# lo.net
KiCad netlist of a schematic drawn in EAGLE
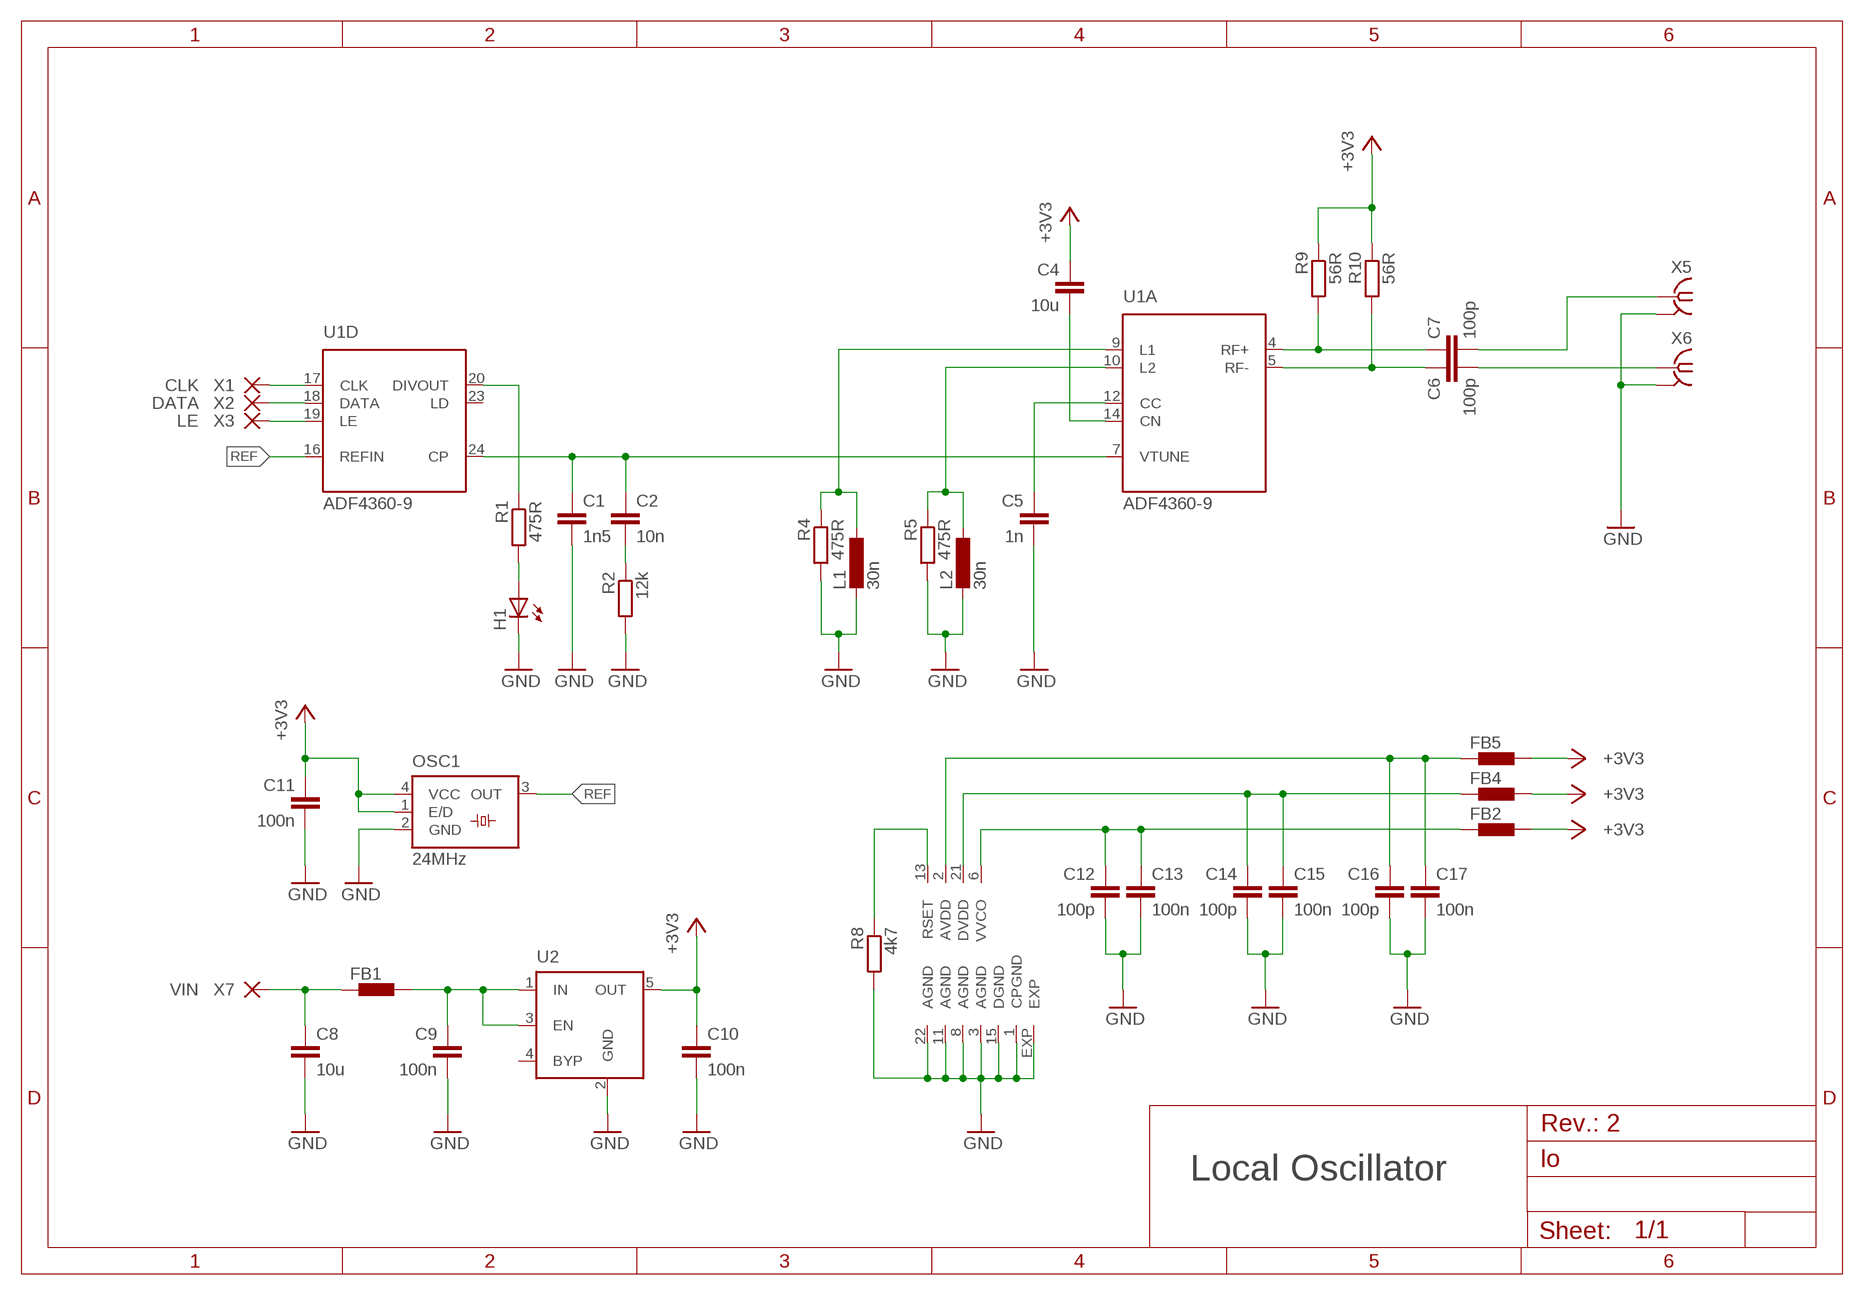
[diagram p0: schematic, sheet 1]

(export (version "E")
  (design (tool "Eeschema 10.0.6"))
  (components
    (comp (ref "C1")
      (value "1n5")
      (footprint "eagle-import:C0402")
      (libsource (lib "eagle-import") (part "C-EUC0402"))
    )
    (comp (ref "C2")
      (value "10n")
      (footprint "eagle-import:C0603")
      (libsource (lib "eagle-import") (part "C-EUC0603"))
    )
    (comp (ref "C4")
      (value "10u")
      (footprint "eagle-import:C0805")
      (libsource (lib "eagle-import") (part "C-EUC0805"))
    )
    (comp (ref "C5")
      (value "1n")
      (footprint "eagle-import:C0603")
      (libsource (lib "eagle-import") (part "C-EUC0603"))
    )
    (comp (ref "C6")
      (value "100p")
      (footprint "eagle-import:C0402")
      (libsource (lib "eagle-import") (part "C-EUC0402"))
    )
    (comp (ref "C7")
      (value "100p")
      (footprint "eagle-import:C0402")
      (libsource (lib "eagle-import") (part "C-EUC0402"))
    )
    (comp (ref "C8")
      (value "10u")
      (footprint "eagle-import:C0805")
      (libsource (lib "eagle-import") (part "C-EUC0805"))
    )
    (comp (ref "C9")
      (value "100n")
      (footprint "eagle-import:C0603")
      (libsource (lib "eagle-import") (part "C-EUC0603"))
    )
    (comp (ref "C10")
      (value "100n")
      (footprint "eagle-import:C0603")
      (libsource (lib "eagle-import") (part "C-EUC0603"))
    )
    (comp (ref "C11")
      (value "100n")
      (footprint "eagle-import:C0603")
      (libsource (lib "eagle-import") (part "C-EUC0603"))
    )
    (comp (ref "C12")
      (value "100p")
      (footprint "eagle-import:C0603")
      (libsource (lib "eagle-import") (part "C-EUC0603"))
    )
    (comp (ref "C13")
      (value "100n")
      (footprint "eagle-import:C0603")
      (libsource (lib "eagle-import") (part "C-EUC0603"))
    )
    (comp (ref "C14")
      (value "100p")
      (footprint "eagle-import:C0603")
      (libsource (lib "eagle-import") (part "C-EUC0603"))
    )
    (comp (ref "C15")
      (value "100n")
      (footprint "eagle-import:C0603")
      (libsource (lib "eagle-import") (part "C-EUC0603"))
    )
    (comp (ref "C16")
      (value "100p")
      (footprint "eagle-import:C0603")
      (libsource (lib "eagle-import") (part "C-EUC0603"))
    )
    (comp (ref "C17")
      (value "100n")
      (footprint "eagle-import:C0603")
      (libsource (lib "eagle-import") (part "C-EUC0603"))
    )
    (comp (ref "FB1")
      (value "BML15H")
      (footprint "eagle-import:R0603")
      (libsource (lib "eagle-import") (part "BML15H"))
    )
    (comp (ref "FB2")
      (value "BML15H")
      (footprint "eagle-import:R0603")
      (libsource (lib "eagle-import") (part "BML15H"))
    )
    (comp (ref "FB4")
      (value "BML15H")
      (footprint "eagle-import:R0603")
      (libsource (lib "eagle-import") (part "BML15H"))
    )
    (comp (ref "FB5")
      (value "BML15H")
      (footprint "eagle-import:R0603")
      (libsource (lib "eagle-import") (part "BML15H"))
    )
    (comp (ref "H1")
      (value "PL006-WCR13")
      (footprint "eagle-import:SOT23")
      (libsource (lib "eagle-import") (part "PL006-WCR13"))
    )
    (comp (ref "L1")
      (value "30n")
      (footprint "eagle-import:L2012C")
      (libsource (lib "eagle-import") (part "L-EUL2012C"))
    )
    (comp (ref "L2")
      (value "30n")
      (footprint "eagle-import:L2012C")
      (libsource (lib "eagle-import") (part "L-EUL2012C"))
    )
    (comp (ref "OSC1")
      (value "24MHz")
      (footprint "eagle-import:SM77H")
      (libsource (lib "eagle-import") (part "SM77H"))
    )
    (comp (ref "R1")
      (value "475R")
      (footprint "eagle-import:R1206")
      (libsource (lib "eagle-import") (part "R-EU_R1206"))
    )
    (comp (ref "R2")
      (value "12k")
      (footprint "eagle-import:R0603")
      (libsource (lib "eagle-import") (part "R-EU_R0603"))
    )
    (comp (ref "R4")
      (value "475R")
      (footprint "eagle-import:R0603")
      (libsource (lib "eagle-import") (part "R-EU_R0603"))
    )
    (comp (ref "R5")
      (value "475R")
      (footprint "eagle-import:R0603")
      (libsource (lib "eagle-import") (part "R-EU_R0603"))
    )
    (comp (ref "R8")
      (value "4k7")
      (footprint "eagle-import:R0603")
      (libsource (lib "eagle-import") (part "R-EU_R0603"))
    )
    (comp (ref "R9")
      (value "56R")
      (footprint "eagle-import:R0603")
      (libsource (lib "eagle-import") (part "R-EU_R0603"))
    )
    (comp (ref "R10")
      (value "56R")
      (footprint "eagle-import:R0603")
      (libsource (lib "eagle-import") (part "R-EU_R0603"))
    )
    (comp (ref "U1")
      (value "ADF4360-9")
      (footprint "eagle-import:LFCSP24")
      (libsource (lib "eagle-import") (part "ADF4360"))
    )
    (comp (ref "U2")
      (value "MIC5219XX")
      (footprint "eagle-import:SOT23-5")
      (libsource (lib "eagle-import") (part "MIC5219XX"))
    )
    (comp (ref "X1")
      (value "CLK")
      (footprint "eagle-import:SMD1,27-2,54")
      (libsource (lib "eagle-import") (part "SMD2"))
    )
    (comp (ref "X2")
      (value "DATA")
      (footprint "eagle-import:SMD1,27-2,54")
      (libsource (lib "eagle-import") (part "SMD2"))
    )
    (comp (ref "X3")
      (value "LE")
      (footprint "eagle-import:SMD1,27-2,54")
      (libsource (lib "eagle-import") (part "SMD2"))
    )
    (comp (ref "X5")
      (value "SMA-142-0701-881/886")
      (footprint "eagle-import:J502-ND-142-0701-881_886")
      (fields (field (name "MF") "JOHNSON COMPONENTS") (field (name "MPN") "142-0701-881"))
      (libsource (lib "eagle-import") (part "SMA-142-0701-881/886"))
    )
    (comp (ref "X6")
      (value "SMA-142-0701-881/886")
      (footprint "eagle-import:J502-ND-142-0701-881_886")
      (fields (field (name "MF") "JOHNSON COMPONENTS") (field (name "MPN") "142-0701-881"))
      (libsource (lib "eagle-import") (part "SMA-142-0701-881/886"))
    )
    (comp (ref "X7")
      (value "VIN")
      (footprint "eagle-import:SMD1,27-2,54")
      (libsource (lib "eagle-import") (part "SMD2"))
    )
  )
  (nets
    (net (code "1") (name "+3V3") (class "Default")
      (node (ref "C10") (pin "1") (pinfunction "1_1") (pintype "passive"))
      (node (ref "C11") (pin "1") (pinfunction "1_1") (pintype "passive"))
      (node (ref "C4") (pin "1") (pinfunction "1_1") (pintype "passive"))
      (node (ref "FB2") (pin "2") (pinfunction "2_2") (pintype "passive"))
      (node (ref "FB4") (pin "2") (pinfunction "2_2") (pintype "passive"))
      (node (ref "FB5") (pin "2") (pinfunction "2_2") (pintype "passive"))
      (node (ref "OSC1") (pin "1") (pinfunction "E/D_1") (pintype "input"))
      (node (ref "OSC1") (pin "4") (pinfunction "VCC_4") (pintype "power_in"))
      (node (ref "R10") (pin "1") (pinfunction "1_1") (pintype "passive"))
      (node (ref "R9") (pin "1") (pinfunction "1_1") (pintype "passive"))
      (node (ref "U2") (pin "5") (pinfunction "OUT_5") (pintype "output"))
    )
    (net (code "2") (name "GND") (class "Default")
      (node (ref "C1") (pin "2") (pinfunction "2_2") (pintype "passive"))
      (node (ref "C10") (pin "2") (pinfunction "2_2") (pintype "passive"))
      (node (ref "C11") (pin "2") (pinfunction "2_2") (pintype "passive"))
      (node (ref "C12") (pin "2") (pinfunction "2_2") (pintype "passive"))
      (node (ref "C13") (pin "2") (pinfunction "2_2") (pintype "passive"))
      (node (ref "C14") (pin "2") (pinfunction "2_2") (pintype "passive"))
      (node (ref "C15") (pin "2") (pinfunction "2_2") (pintype "passive"))
      (node (ref "C16") (pin "2") (pinfunction "2_2") (pintype "passive"))
      (node (ref "C17") (pin "2") (pinfunction "2_2") (pintype "passive"))
      (node (ref "C5") (pin "2") (pinfunction "2_2") (pintype "passive"))
      (node (ref "C8") (pin "2") (pinfunction "2_2") (pintype "passive"))
      (node (ref "C9") (pin "2") (pinfunction "2_2") (pintype "passive"))
      (node (ref "H1") (pin "3") (pinfunction "C_3") (pintype "passive"))
      (node (ref "L1") (pin "2") (pinfunction "2_2") (pintype "passive"))
      (node (ref "L2") (pin "2") (pinfunction "2_2") (pintype "passive"))
      (node (ref "OSC1") (pin "2") (pinfunction "GND_2") (pintype "power_in"))
      (node (ref "R2") (pin "2") (pinfunction "2_2") (pintype "passive"))
      (node (ref "R4") (pin "2") (pinfunction "2_2") (pintype "passive"))
      (node (ref "R5") (pin "2") (pinfunction "2_2") (pintype "passive"))
      (node (ref "R8") (pin "2") (pinfunction "2_2") (pintype "passive"))
      (node (ref "U1") (pin "1") (pinfunction "CPGND_1") (pintype "power_in"))
      (node (ref "U1") (pin "11") (pinfunction "AGND_11") (pintype "power_in"))
      (node (ref "U1") (pin "15") (pinfunction "DGND_15") (pintype "power_in"))
      (node (ref "U1") (pin "22") (pinfunction "AGND_22") (pintype "power_in"))
      (node (ref "U1") (pin "3") (pinfunction "AGND_3") (pintype "power_in"))
      (node (ref "U1") (pin "8") (pinfunction "AGND_8") (pintype "power_in"))
      (node (ref "U1") (pin "EXP") (pinfunction "EXP_EXP") (pintype "power_in"))
      (node (ref "U2") (pin "2") (pinfunction "GND_2") (pintype "power_in"))
      (node (ref "X5") (pin "G@1") (pinfunction "GND_G@1") (pintype "power_in"))
      (node (ref "X6") (pin "G@1") (pinfunction "GND_G@1") (pintype "power_in"))
    )
    (net (code "3") (name "Net-(C2-Pad2)") (class "Default")
      (node (ref "C2") (pin "2") (pinfunction "2_2") (pintype "passive"))
      (node (ref "R2") (pin "1") (pinfunction "1_1") (pintype "passive"))
    )
    (net (code "4") (name "Net-(C6-Pad2)") (class "Default")
      (node (ref "C6") (pin "2") (pinfunction "2_2") (pintype "passive"))
      (node (ref "X6") (pin "1") (pinfunction "1_1") (pintype "passive"))
    )
    (net (code "5") (name "Net-(C7-Pad2)") (class "Default")
      (node (ref "C7") (pin "2") (pinfunction "2_2") (pintype "passive"))
      (node (ref "X5") (pin "1") (pinfunction "1_1") (pintype "passive"))
    )
    (net (code "6") (name "Net-(H1-A)") (class "Default")
      (node (ref "H1") (pin "1") (pinfunction "A_1") (pintype "passive"))
      (node (ref "R1") (pin "2") (pinfunction "2_2") (pintype "passive"))
    )
    (net (code "7") (name "Net-(U1A-CC)") (class "Default")
      (node (ref "C5") (pin "1") (pinfunction "1_1") (pintype "passive"))
      (node (ref "U1") (pin "12") (pinfunction "CC_12") (pintype "passive"))
    )
    (net (code "8") (name "Net-(U1A-CN)") (class "Default")
      (node (ref "C4") (pin "2") (pinfunction "2_2") (pintype "passive"))
      (node (ref "U1") (pin "14") (pinfunction "CN_14") (pintype "passive"))
    )
    (net (code "9") (name "Net-(U1A-L1)") (class "Default")
      (node (ref "L1") (pin "1") (pinfunction "1_1") (pintype "passive"))
      (node (ref "R4") (pin "1") (pinfunction "1_1") (pintype "passive"))
      (node (ref "U1") (pin "9") (pinfunction "L1_9") (pintype "passive"))
    )
    (net (code "10") (name "Net-(U1A-L2)") (class "Default")
      (node (ref "L2") (pin "1") (pinfunction "1_1") (pintype "passive"))
      (node (ref "R5") (pin "1") (pinfunction "1_1") (pintype "passive"))
      (node (ref "U1") (pin "10") (pinfunction "L2_10") (pintype "passive"))
    )
    (net (code "11") (name "Net-(U1A-RF+)") (class "Default")
      (node (ref "C7") (pin "1") (pinfunction "1_1") (pintype "passive"))
      (node (ref "R9") (pin "2") (pinfunction "2_2") (pintype "passive"))
      (node (ref "U1") (pin "4") (pinfunction "RF+_4") (pintype "output"))
    )
    (net (code "12") (name "Net-(U1A-RF-)") (class "Default")
      (node (ref "C6") (pin "1") (pinfunction "1_1") (pintype "passive"))
      (node (ref "R10") (pin "2") (pinfunction "2_2") (pintype "passive"))
      (node (ref "U1") (pin "5") (pinfunction "RF-_5") (pintype "output"))
    )
    (net (code "13") (name "Net-(U1A-VTUNE)") (class "Default")
      (node (ref "C1") (pin "1") (pinfunction "1_1") (pintype "passive"))
      (node (ref "C2") (pin "1") (pinfunction "1_1") (pintype "passive"))
      (node (ref "U1") (pin "24") (pinfunction "CP_24") (pintype "output"))
      (node (ref "U1") (pin "7") (pinfunction "VTUNE_7") (pintype "input"))
    )
    (net (code "14") (name "Net-(U1B-CLK)") (class "Default")
      (node (ref "U1") (pin "17") (pinfunction "CLK_17") (pintype "input"))
      (node (ref "X1") (pin "1") (pinfunction "P_1") (pintype "passive"))
    )
    (net (code "15") (name "Net-(U1B-DATA)") (class "Default")
      (node (ref "U1") (pin "18") (pinfunction "DATA_18") (pintype "input"))
      (node (ref "X2") (pin "1") (pinfunction "P_1") (pintype "passive"))
    )
    (net (code "16") (name "Net-(U1B-DIVOUT)") (class "Default")
      (node (ref "R1") (pin "1") (pinfunction "1_1") (pintype "passive"))
      (node (ref "U1") (pin "20") (pinfunction "DIVOUT_20") (pintype "output"))
    )
    (net (code "17") (name "Net-(U1B-LE)") (class "Default")
      (node (ref "U1") (pin "19") (pinfunction "LE_19") (pintype "input"))
      (node (ref "X3") (pin "1") (pinfunction "P_1") (pintype "passive"))
    )
    (net (code "18") (name "Net-(U1C-AVDD)") (class "Default")
      (node (ref "C16") (pin "1") (pinfunction "1_1") (pintype "passive"))
      (node (ref "C17") (pin "1") (pinfunction "1_1") (pintype "passive"))
      (node (ref "FB5") (pin "1") (pinfunction "1_1") (pintype "passive"))
      (node (ref "U1") (pin "2") (pinfunction "AVDD_2") (pintype "power_in"))
    )
    (net (code "19") (name "Net-(U1C-DVDD)") (class "Default")
      (node (ref "C14") (pin "1") (pinfunction "1_1") (pintype "passive"))
      (node (ref "C15") (pin "1") (pinfunction "1_1") (pintype "passive"))
      (node (ref "FB4") (pin "1") (pinfunction "1_1") (pintype "passive"))
      (node (ref "U1") (pin "21") (pinfunction "DVDD_21") (pintype "power_in"))
    )
    (net (code "20") (name "Net-(U1C-RSET)") (class "Default")
      (node (ref "R8") (pin "1") (pinfunction "1_1") (pintype "passive"))
      (node (ref "U1") (pin "13") (pinfunction "RSET_13") (pintype "power_in"))
    )
    (net (code "21") (name "Net-(U1C-VVCO)") (class "Default")
      (node (ref "C12") (pin "1") (pinfunction "1_1") (pintype "passive"))
      (node (ref "C13") (pin "1") (pinfunction "1_1") (pintype "passive"))
      (node (ref "FB2") (pin "1") (pinfunction "1_1") (pintype "passive"))
      (node (ref "U1") (pin "6") (pinfunction "VVCO_6") (pintype "power_in"))
    )
    (net (code "22") (name "Net-(U2-EN)") (class "Default")
      (node (ref "C9") (pin "1") (pinfunction "1_1") (pintype "passive"))
      (node (ref "FB1") (pin "2") (pinfunction "2_2") (pintype "passive"))
      (node (ref "U2") (pin "1") (pinfunction "IN_1") (pintype "input"))
      (node (ref "U2") (pin "3") (pinfunction "EN_3") (pintype "input"))
    )
    (net (code "23") (name "Net-(X7-P)") (class "Default")
      (node (ref "C8") (pin "1") (pinfunction "1_1") (pintype "passive"))
      (node (ref "FB1") (pin "1") (pinfunction "1_1") (pintype "passive"))
      (node (ref "X7") (pin "1") (pinfunction "P_1") (pintype "passive"))
    )
    (net (code "24") (name "REF") (class "Default")
      (node (ref "OSC1") (pin "3") (pinfunction "OUT_3") (pintype "output"))
      (node (ref "U1") (pin "16") (pinfunction "REFIN_16") (pintype "input"))
    )
    (net (code "25") (name "unconnected-(U1B-LD-Pad23)") (class "Default")
      (node (ref "U1") (pin "23") (pinfunction "LD_23") (pintype "output"))
    )
    (net (code "26") (name "unconnected-(U2-BYP-Pad4)") (class "Default")
      (node (ref "U2") (pin "4") (pinfunction "BYP_4") (pintype "passive"))
    )
  )
)
